# Joystick.net
KiCad netlist of a schematic drawn in EAGLE
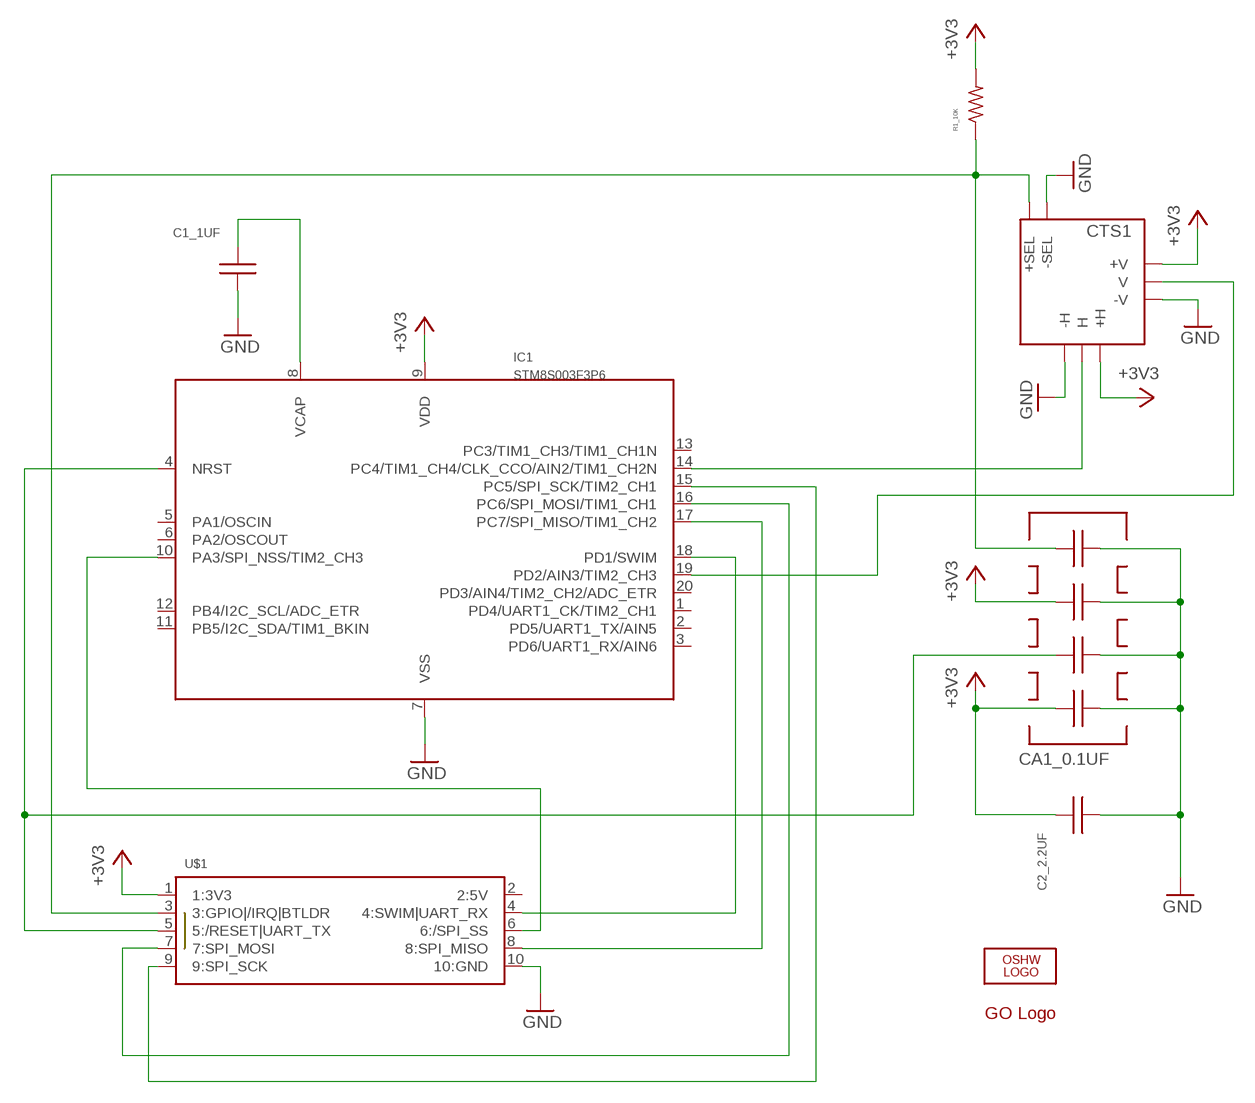
[diagram p0: schematic, sheet 1]

(export (version "E")
  (design (tool "Eeschema 10.0.6"))
  (components
    (comp (ref "C1_1UF")
      (value "MURATA_GRM_1UF_CER_CAP_0805")
      (footprint "eagle-import:0805")
      (libsource (lib "eagle-import") (part "MURATA_GRM_1UF_CER_CAP_0805"))
    )
    (comp (ref "C2_2.2UF")
      (value "CAP_CER_2.2UF_0805")
      (footprint "eagle-import:0805")
      (libsource (lib "eagle-import") (part "CAP_CER_2.2UF_0805"))
    )
    (comp (ref "CA1_0.1UF")
      (value "TAYIO-YUDEN_0.1UF_CAP_ARRAY_0805")
      (footprint "eagle-import:TAYIO-YUDEN_CAP_ARRAY_4_CIRCUITS_0805")
      (libsource (lib "eagle-import") (part "TAYIO-YUDEN_0.1UF_CAP_ARRAY_0805"))
    )
    (comp (ref "CTS1")
      (value "CTS252B103A60NB10K")
      (footprint "eagle-import:JOYSTICK+SWITCH")
      (libsource (lib "eagle-import") (part "CTS252B103A60NB10K"))
    )
    (comp (ref "IC1")
      (value "STM8S003F3P6")
      (footprint "eagle-import:STM8S003F3P6")
      (libsource (lib "eagle-import") (part "STM8S003F3P6"))
    )
    (comp (ref "LOGO1")
      (value "OSHW_LOGO_8MILX0150-NT")
      (footprint "eagle-import:OSHW_8X150_NOTEXT")
      (libsource (lib "eagle-import") (part "OSHW_LOGO_8MILX0150-NT"))
    )
    (comp (ref "R1_10K")
      (value "RESISTOR_0805")
      (footprint "eagle-import:0805")
      (libsource (lib "eagle-import") (part "RESISTOR_0805"))
    )
    (comp (ref "U$1")
      (value "GO_CONNECTOR")
      (footprint "eagle-import:FCI-1.27X1.27MM_10PIN_HEADER_SHROUDED_SMT")
      (libsource (lib "eagle-import") (part "GO_CONNECTOR"))
    )
    (comp (ref "U$5")
      (value "GO_LOGO")
      (footprint "eagle-import:GO_LOGO")
      (libsource (lib "eagle-import") (part "GO_LOGO"))
    )
  )
  (nets
    (net (code "1") (name "+3V3") (class "Default")
      (node (ref "C2_2.2UF") (pin "A") (pinfunction "1_A") (pintype "passive"))
      (node (ref "CA1_0.1UF") (pin "4") (pinfunction "4_4") (pintype "passive"))
      (node (ref "CA1_0.1UF") (pin "8") (pinfunction "8_8") (pintype "passive"))
      (node (ref "CTS1") (pin "H+") (pinfunction "+H_H+") (pintype "power_in"))
      (node (ref "CTS1") (pin "V+") (pinfunction "+V_V+") (pintype "power_in"))
      (node (ref "IC1") (pin "9") (pinfunction "VDD_9") (pintype "bidirectional"))
      (node (ref "R1_10K") (pin "K") (pinfunction "2_K") (pintype "passive"))
      (node (ref "U$1") (pin "1") (pinfunction "1:3V3_1") (pintype "power_in"))
    )
    (net (code "2") (name "/2:5V") (class "Default")
      (node (ref "U$1") (pin "2") (pinfunction "2:5V_2") (pintype "power_in"))
    )
    (net (code "3") (name "GND") (class "Default")
      (node (ref "C1_1UF") (pin "K") (pinfunction "2_K") (pintype "passive"))
      (node (ref "C2_2.2UF") (pin "K") (pinfunction "2_K") (pintype "passive"))
      (node (ref "CA1_0.1UF") (pin "1") (pinfunction "1_1") (pintype "passive"))
      (node (ref "CA1_0.1UF") (pin "3") (pinfunction "3_3") (pintype "passive"))
      (node (ref "CA1_0.1UF") (pin "5") (pinfunction "5_5") (pintype "passive"))
      (node (ref "CA1_0.1UF") (pin "7") (pinfunction "7_7") (pintype "passive"))
      (node (ref "CTS1") (pin "H-") (pinfunction "-H_H-") (pintype "passive"))
      (node (ref "CTS1") (pin "SEL-") (pinfunction "-SEL_SEL-") (pintype "passive"))
      (node (ref "CTS1") (pin "V-") (pinfunction "-V_V-") (pintype "passive"))
      (node (ref "IC1") (pin "7") (pinfunction "VSS_7") (pintype "bidirectional"))
      (node (ref "U$1") (pin "10") (pinfunction "10:GND_10") (pintype "passive"))
    )
    (net (code "4") (name "Net-(C1_1UF-1)") (class "Default")
      (node (ref "C1_1UF") (pin "A") (pinfunction "1_A") (pintype "passive"))
      (node (ref "IC1") (pin "8") (pinfunction "VCAP_8") (pintype "bidirectional"))
    )
    (net (code "5") (name "Net-(CTS1-+SEL)") (class "Default")
      (node (ref "CA1_0.1UF") (pin "6") (pinfunction "6_6") (pintype "passive"))
      (node (ref "CTS1") (pin "SEL+") (pinfunction "+SEL_SEL+") (pintype "power_in"))
      (node (ref "R1_10K") (pin "A") (pinfunction "1_A") (pintype "passive"))
      (node (ref "U$1") (pin "3") (pinfunction "3:GPIO|/IRQ|BTLDR_3") (pintype "bidirectional"))
    )
    (net (code "6") (name "Net-(CTS1-H)") (class "Default")
      (node (ref "CTS1") (pin "H-OUT") (pinfunction "H_H-OUT") (pintype "output"))
      (node (ref "IC1") (pin "14") (pinfunction "PC4/TIM1_CH4/CLK_CCO/AIN2/TIM1_CH2N_14") (pintype "bidirectional"))
    )
    (net (code "7") (name "Net-(CTS1-V)") (class "Default")
      (node (ref "CTS1") (pin "V-OUT") (pinfunction "V_V-OUT") (pintype "output"))
      (node (ref "IC1") (pin "19") (pinfunction "PD2/AIN3/TIM2_CH3_19") (pintype "bidirectional"))
    )
    (net (code "8") (name "Net-(IC1-NRST)") (class "Default")
      (node (ref "CA1_0.1UF") (pin "2") (pinfunction "2_2") (pintype "passive"))
      (node (ref "IC1") (pin "4") (pinfunction "NRST_4") (pintype "bidirectional"))
      (node (ref "U$1") (pin "5") (pinfunction "5:/RESET|UART_TX_5") (pintype "bidirectional"))
    )
    (net (code "9") (name "Net-(IC1-PA3{slash}SPI_NSS{slash}TIM2_CH3)") (class "Default")
      (node (ref "IC1") (pin "10") (pinfunction "PA3/SPI_NSS/TIM2_CH3_10") (pintype "bidirectional"))
      (node (ref "U$1") (pin "6") (pinfunction "6:/SPI_SS_6") (pintype "bidirectional"))
    )
    (net (code "10") (name "Net-(IC1-PC5{slash}SPI_SCK{slash}TIM2_CH1)") (class "Default")
      (node (ref "IC1") (pin "15") (pinfunction "PC5/SPI_SCK/TIM2_CH1_15") (pintype "bidirectional"))
      (node (ref "U$1") (pin "9") (pinfunction "9:SPI_SCK_9") (pintype "bidirectional"))
    )
    (net (code "11") (name "Net-(IC1-PC6{slash}SPI_MOSI{slash}TIM1_CH1)") (class "Default")
      (node (ref "IC1") (pin "16") (pinfunction "PC6/SPI_MOSI/TIM1_CH1_16") (pintype "bidirectional"))
      (node (ref "U$1") (pin "7") (pinfunction "7:SPI_MOSI_7") (pintype "bidirectional"))
    )
    (net (code "12") (name "Net-(IC1-PC7{slash}SPI_MISO{slash}TIM1_CH2)") (class "Default")
      (node (ref "IC1") (pin "17") (pinfunction "PC7/SPI_MISO/TIM1_CH2_17") (pintype "bidirectional"))
      (node (ref "U$1") (pin "8") (pinfunction "8:SPI_MISO_8") (pintype "bidirectional"))
    )
    (net (code "13") (name "Net-(IC1-PD1{slash}SWIM)") (class "Default")
      (node (ref "IC1") (pin "18") (pinfunction "PD1/SWIM_18") (pintype "bidirectional"))
      (node (ref "U$1") (pin "4") (pinfunction "4:SWIM|UART_RX_4") (pintype "bidirectional"))
    )
    (net (code "14") (name "unconnected-(IC1-PA1{slash}OSCIN-Pad5)") (class "Default")
      (node (ref "IC1") (pin "5") (pinfunction "PA1/OSCIN_5") (pintype "bidirectional"))
    )
    (net (code "15") (name "unconnected-(IC1-PA2{slash}OSCOUT-Pad6)") (class "Default")
      (node (ref "IC1") (pin "6") (pinfunction "PA2/OSCOUT_6") (pintype "bidirectional"))
    )
    (net (code "16") (name "unconnected-(IC1-PB4{slash}I2C_SCL{slash}ADC_ETR-Pad12)") (class "Default")
      (node (ref "IC1") (pin "12") (pinfunction "PB4/I2C_SCL/ADC_ETR_12") (pintype "bidirectional"))
    )
    (net (code "17") (name "unconnected-(IC1-PB5{slash}I2C_SDA{slash}TIM1_BKIN-Pad11)") (class "Default")
      (node (ref "IC1") (pin "11") (pinfunction "PB5/I2C_SDA/TIM1_BKIN_11") (pintype "bidirectional"))
    )
    (net (code "18") (name "unconnected-(IC1-PC3{slash}TIM1_CH3{slash}TIM1_CH1N-Pad13)") (class "Default")
      (node (ref "IC1") (pin "13") (pinfunction "PC3/TIM1_CH3/TIM1_CH1N_13") (pintype "bidirectional"))
    )
    (net (code "19") (name "unconnected-(IC1-PD3{slash}AIN4{slash}TIM2_CH2{slash}ADC_ETR-Pad20)") (class "Default")
      (node (ref "IC1") (pin "20") (pinfunction "PD3/AIN4/TIM2_CH2/ADC_ETR_20") (pintype "bidirectional"))
    )
    (net (code "20") (name "unconnected-(IC1-PD4{slash}UART1_CK{slash}TIM2_CH1-Pad1)") (class "Default")
      (node (ref "IC1") (pin "1") (pinfunction "PD4/UART1_CK/TIM2_CH1_1") (pintype "bidirectional"))
    )
    (net (code "21") (name "unconnected-(IC1-PD5{slash}UART1_TX{slash}AIN5-Pad2)") (class "Default")
      (node (ref "IC1") (pin "2") (pinfunction "PD5/UART1_TX/AIN5_2") (pintype "bidirectional"))
    )
    (net (code "22") (name "unconnected-(IC1-PD6{slash}UART1_RX{slash}AIN6-Pad3)") (class "Default")
      (node (ref "IC1") (pin "3") (pinfunction "PD6/UART1_RX/AIN6_3") (pintype "bidirectional"))
    )
  )
)
